# PS_mainPrint.net
KiCad netlist of a schematic drawn in Altium Designer
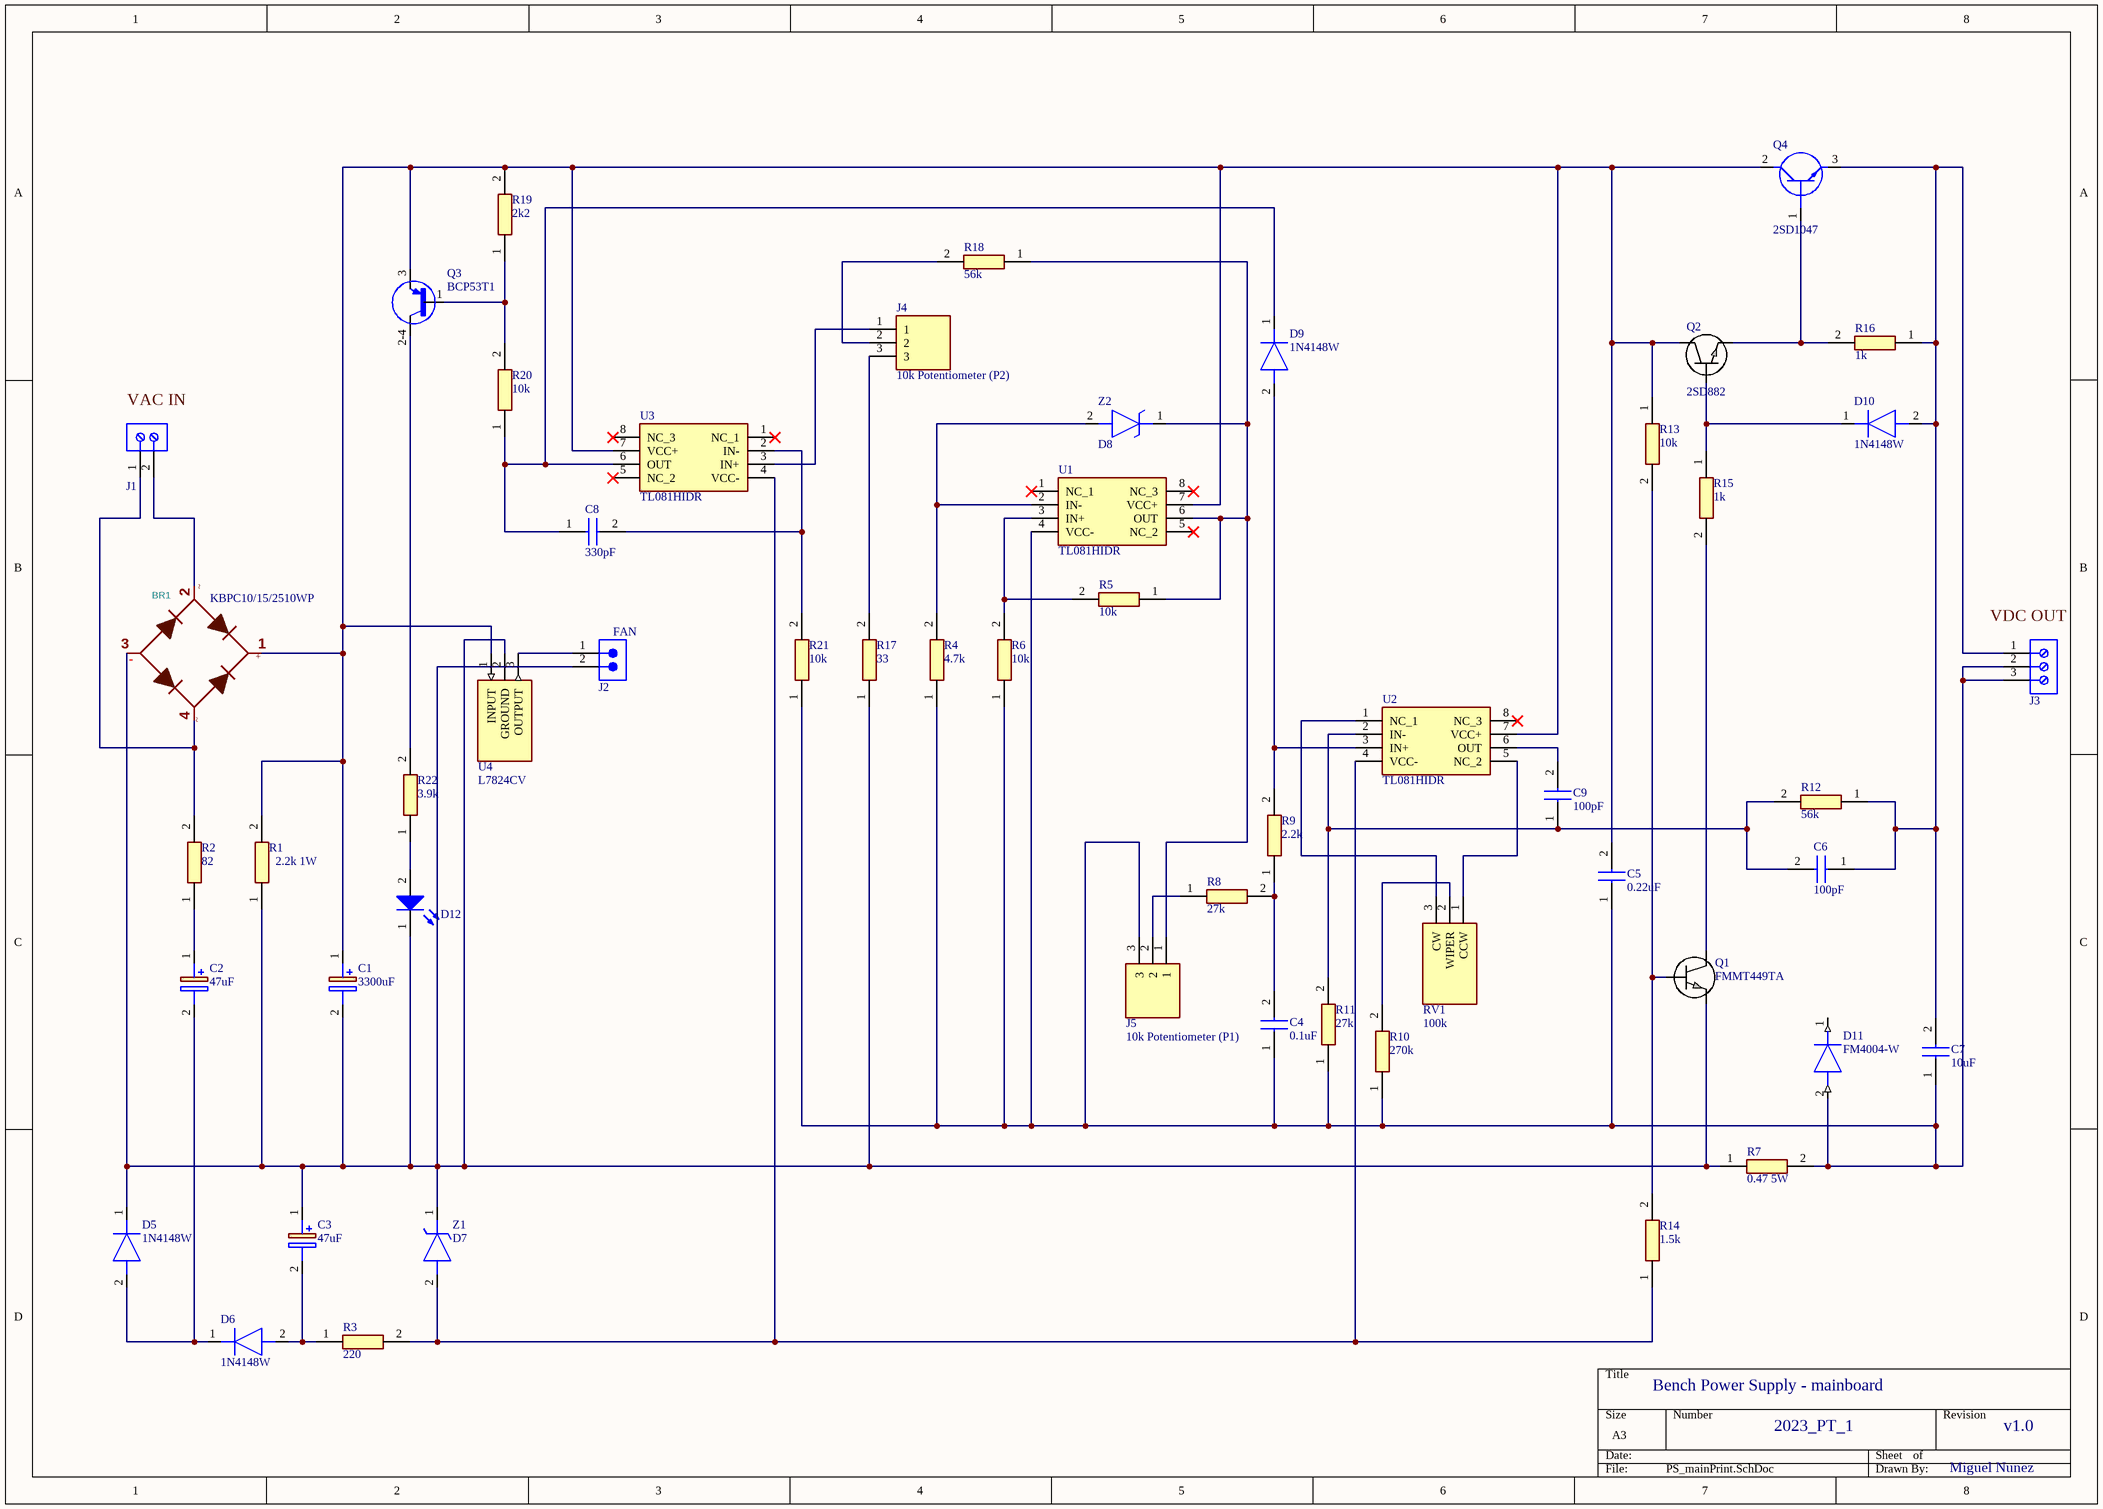
[diagram p0: PS_mainPrint.SchDoc]

(export (version "E")
  (design (tool "Eeschema 10.0.6"))
  (components
    (comp (ref "BR1")
      (value "KBPC10/15/2510WP")
      (footprint "PS_PcbLib:KBPCxxxxWP")
      (libsource (lib "PS_SchematicLib") (part "Bridge_1ph"))
    )
    (comp (ref "C1")
      (value "3300uF")
      (footprint "PS_PcbLib:CAPPRD500W60D1050H1350")
      (description "Capacitor Polarised MAL213668479E3")
      (fields
        (field (name "MANUFACTURER_PART_NUMBER") "MAL213668479E3")
        (field (name "MOUSER PART NUMBER") "594-2222-136-68479")
      )
      (libsource (lib "PS_SchematicLib") (part "MAL213668479E3"))
    )
    (comp (ref "C2")
      (value "47uF")
      (footprint "PS_PcbLib:CAPPRD750W80D1850H4250")
      (description "Capacitor Polarised MAL215051332E3")
      (fields
        (field (name "MANUFACTURER_PART_NUMBER") "MAL215051332E3")
        (field (name "MOUSER PART NUMBER") "594-MAL215051332E3")
      )
      (libsource (lib "PS_SchematicLib") (part "MAL215051332E3"))
    )
    (comp (ref "C3")
      (value "47uF")
      (footprint "PS_PcbLib:CAPPRD750W80D1850H4250")
      (description "Capacitor Polarised MAL215051332E3")
      (fields
        (field (name "MANUFACTURER_PART_NUMBER") "MAL215051332E3")
        (field (name "MOUSER PART NUMBER") "594-MAL215051332E3")
      )
      (libsource (lib "PS_SchematicLib") (part "MAL215051332E3"))
    )
    (comp (ref "C4")
      (value "0.1uF")
      (footprint "PS_PcbLib:CAPC2012X145N")
      (description "Capacitor C2012X7T2E104K125AE")
      (fields
        (field (name "MANUFACTURER_PART_NUMBER") "C2012X7T2E104K125AE")
        (field (name "MOUSER PART NUMBER") "810-C2012X7T2E104KST")
      )
      (libsource (lib "PS_SchematicLib") (part "Capacitor cer. 0805"))
    )
    (comp (ref "C5")
      (value "0.22uF")
      (footprint "PS_PcbLib:CAPC2012X145N")
      (description "Capacitor C2012X7T2E104K125AE")
      (fields
        (field (name "MANUFACTURER_PART_NUMBER") "C2012X7T2E104K125AE")
        (field (name "MOUSER PART NUMBER") "810-C2012X7T2E104KST")
      )
      (libsource (lib "PS_SchematicLib") (part "Capacitor cer. 0805"))
    )
    (comp (ref "C6")
      (value "100pF")
      (footprint "PS_PcbLib:CAPC2012X145N")
      (description "Capacitor C2012X7T2E104K125AE")
      (fields
        (field (name "MANUFACTURER_PART_NUMBER") "C2012X7T2E104K125AE")
        (field (name "MOUSER PART NUMBER") "810-C2012X7T2E104KST")
      )
      (libsource (lib "PS_SchematicLib") (part "Capacitor cer. 0805"))
    )
    (comp (ref "C7")
      (value "10uF")
      (footprint "PS_PcbLib:CAPC2012X145N")
      (description "Capacitor C2012X7T2E104K125AE")
      (fields
        (field (name "MANUFACTURER_PART_NUMBER") "C2012X7T2E104K125AE")
        (field (name "MOUSER PART NUMBER") "810-C2012X7T2E104KST")
      )
      (libsource (lib "PS_SchematicLib") (part "Capacitor cer. 0805"))
    )
    (comp (ref "C8")
      (value "330pF")
      (footprint "PS_PcbLib:CAPC2012X145N")
      (description "Capacitor C2012X7T2E104K125AE")
      (fields
        (field (name "MANUFACTURER_PART_NUMBER") "C2012X7T2E104K125AE")
        (field (name "MOUSER PART NUMBER") "810-C2012X7T2E104KST")
      )
      (libsource (lib "PS_SchematicLib") (part "Capacitor cer. 0805"))
    )
    (comp (ref "C9")
      (value "100pF")
      (footprint "PS_PcbLib:CAPC2012X145N")
      (description "Capacitor C2012X7T2E104K125AE")
      (fields
        (field (name "MANUFACTURER_PART_NUMBER") "C2012X7T2E104K125AE")
        (field (name "MOUSER PART NUMBER") "810-C2012X7T2E104KST")
      )
      (libsource (lib "PS_SchematicLib") (part "Capacitor cer. 0805"))
    )
    (comp (ref "D5")
      (value "1N4148W")
      (footprint "PS_PcbLib:SOD3816X135N")
      (description "Diode 1N4148W_R1_00001")
      (fields
        (field (name "MANUFACTURER_PART_NUMBER") "1N4148W_R1_00001")
        (field (name "MOUSER PART NUMBER") "241-1N4148W_R1_00001")
      )
      (libsource (lib "PS_SchematicLib") (part "1N4148W_R1_00001"))
    )
    (comp (ref "D6")
      (value "1N4148W")
      (footprint "PS_PcbLib:SOD3816X135N")
      (description "Diode 1N4148W_R1_00001")
      (fields
        (field (name "MANUFACTURER_PART_NUMBER") "1N4148W_R1_00001")
        (field (name "MOUSER PART NUMBER") "241-1N4148W_R1_00001")
      )
      (libsource (lib "PS_SchematicLib") (part "1N4148W_R1_00001"))
    )
    (comp (ref "D9")
      (value "1N4148W")
      (footprint "PS_PcbLib:SOD3816X135N")
      (description "Diode 1N4148W_R1_00001")
      (fields
        (field (name "MANUFACTURER_PART_NUMBER") "1N4148W_R1_00001")
        (field (name "MOUSER PART NUMBER") "241-1N4148W_R1_00001")
      )
      (libsource (lib "PS_SchematicLib") (part "1N4148W_R1_00001"))
    )
    (comp (ref "D10")
      (value "1N4148W")
      (footprint "PS_PcbLib:SOD3816X135N")
      (description "Diode 1N4148W_R1_00001")
      (fields
        (field (name "MANUFACTURER_PART_NUMBER") "1N4148W_R1_00001")
        (field (name "MOUSER PART NUMBER") "241-1N4148W_R1_00001")
      )
      (libsource (lib "PS_SchematicLib") (part "1N4148W_R1_00001"))
    )
    (comp (ref "D11")
      (value "FM4004-W")
      (footprint "PS_PcbLib:DIONM5025X231N")
      (description "Diode")
      (fields (field (name "MOUSER PART NUMBER") "583-FM4004"))
      (libsource (lib "PS_SchematicLib") (part "FM4004-W"))
    )
    (comp (ref "D12")
      (value "Blue, 3.2V, 140°")
      (footprint "PS_PcbLib:WL-SMCW_0805_150080xx75000")
      (description "WL-SMCW Mono-color Chip LED Waterclear, size 0805, Blue, 3.2V, 140°")
      (fields
        (field (name "MANUFACTURER PART NUMBER") "150080BS75000")
        (field (name "MANUFACTURER") "Wurth Elektronik")
      )
      (libsource (lib "PS_SchematicLib") (part "150080BS75000"))
    )
    (comp (ref "J1")
      (value "24VAC INPUT")
      (footprint "PS_PcbLib:691103110002")
      (description "WR-TBL Series 1031 Horizontal Entry Modular, THT, pitch 3.5mm, 2p 691103110002")
      (fields
        (field (name "MANUFACTURER PART NUMBER") "691103110002")
        (field (name "MANUFACTURER") "Wurth Elektronik")
      )
      (libsource (lib "PS_SchematicLib") (part "691103110002"))
    )
    (comp (ref "J2")
      (value "FAN")
      (footprint "PS_PcbLib:61900211121")
      (description "WR-WTB THT Male Vertical Locking Header, pitch 2.54mm, 2pins 61900211121")
      (fields
        (field (name "MANUFACTURER PART NUMBER") "61900211121")
        (field (name "MANUFACTURER") "Wurth Elektronik")
      )
      (libsource (lib "PS_SchematicLib") (part "61900211121"))
    )
    (comp (ref "J3")
      (value "TermBlock 3p")
      (footprint "PS_PcbLib:691103110003")
      (description "WR-TBL Series 1031 Horizontal Entry Modular, THT, pitch 3.5mm, 3p  691103110003")
      (fields
        (field (name "MANUFACTURER PART NUMBER") "691103110003")
        (field (name "MANUFACTURER") "Wurth Elektronik")
      )
      (libsource (lib "PS_SchematicLib") (part "691103110003"))
    )
    (comp (ref "J4")
      (value "10k Potentiometer (P2)")
      (footprint "PS_PcbLib:SHDR3W79P0X254_1X3_762X580X1175P")
      (description "Connector 3pin")
      (fields (field (name "MANUFACTURER_PART_NUMBER") "61900311121"))
      (libsource (lib "") (part "61900311121_1"))
    )
    (comp (ref "J5")
      (value "10k Potentiometer (P1)")
      (footprint "PS_PcbLib:SHDR3W79P0X254_1X3_762X580X1175P")
      (description "Connector 3pin")
      (fields (field (name "MANUFACTURER_PART_NUMBER") "61900311121"))
      (libsource (lib "PS_SchematicLib") (part "61900311121"))
    )
    (comp (ref "Q1")
      (value "FMMT449TA")
      (footprint "PS_PcbLib:SOT-23_2P9X1P3_DIO")
      (description "No Description Available")
      (fields (field (name "COPYRIGHT") "Copyright (C) 2023 Ultra Librarian. All rights reserved."))
      (libsource (lib "PS_SchematicLib") (part "FMMT449TA"))
    )
    (comp (ref "Q2")
      (value "2SD882")
      (footprint "PS_PcbLib:SOT-32_STM")
      (description "No Description Available")
      (fields (field (name "COPYRIGHT") "Copyright (C) 2023 Ultra Librarian. All rights reserved."))
      (libsource (lib "PS_SchematicLib") (part "2SD882"))
    )
    (comp (ref "Q3")
      (value "BCP53T1")
      (footprint "PS_PcbLib:TRANS_BCP53T1")
      (description "Bipolar (BJT) Transistor PNP 80 V 1.5 A 50MHz 1.5 W Surface Mount SOT-223 (TO-261)")
      (fields (field (name "MF") "ON Semiconductor"))
      (libsource (lib "PS_SchematicLib") (part "BCP53T1"))
    )
    (comp (ref "Q4")
      (value "2SD1047")
      (footprint "PS_PcbLib:TO545P500X1560X2360-3P")
      (description "Transistor BJT NPN")
      (fields (field (name "MOUSER PART NUMBER") "511-2SD1047"))
      (libsource (lib "PS_SchematicLib") (part "2SD1047"))
    )
    (comp (ref "R1")
      (value "2.2k 1W")
      (footprint "PS_PcbLib:RESC5025X70N")
      (description "Resistor 2.2k 1W CRCW20102K20JNEFHP")
      (fields (field (name "MANUFACTURER_PART_NUMBER") "ESR10EZPJ472"))
      (libsource (lib "") (part "CRCW2010_1"))
    )
    (comp (ref "R2")
      (value "82")
      (footprint "PS_PcbLib:RESC2012X60N")
      (description "Resistor CRCW0805")
      (fields
        (field (name "MANUFACTURER_PART_NUMBER") "CRCW080582R0FKEAHP")
        (field (name "MOUSER PART NUMBER") "71-CRCW080582R0FKEAH")
      )
      (libsource (lib "PS_SchematicLib") (part "CRCW0805"))
    )
    (comp (ref "R3")
      (value "220")
      (footprint "PS_PcbLib:RESC2012X60N")
      (description "Resistor CRCW0805")
      (fields
        (field (name "MANUFACTURER_PART_NUMBER") "CRCW080582R0FKEAHP")
        (field (name "MOUSER PART NUMBER") "71-CRCW080582R0FKEAH")
      )
      (libsource (lib "") (part "CRCW0805_1"))
    )
    (comp (ref "R4")
      (value "4.7k")
      (footprint "PS_PcbLib:RESC2012X60N")
      (description "Resistor CRCW0805")
      (fields
        (field (name "MANUFACTURER_PART_NUMBER") "CRCW080582R0FKEAHP")
        (field (name "MOUSER PART NUMBER") "71-CRCW080582R0FKEAH")
      )
      (libsource (lib "PS_SchematicLib") (part "CRCW0805"))
    )
    (comp (ref "R5")
      (value "10k")
      (footprint "PS_PcbLib:RESC2012X60N")
      (description "Resistor CRCW0805")
      (fields
        (field (name "MANUFACTURER_PART_NUMBER") "CRCW080582R0FKEAHP")
        (field (name "MOUSER PART NUMBER") "71-CRCW080582R0FKEAH")
      )
      (libsource (lib "") (part "CRCW0805_2"))
    )
    (comp (ref "R6")
      (value "10k")
      (footprint "PS_PcbLib:RESC2012X60N")
      (description "Resistor CRCW0805")
      (fields
        (field (name "MANUFACTURER_PART_NUMBER") "CRCW080582R0FKEAHP")
        (field (name "MOUSER PART NUMBER") "71-CRCW080582R0FKEAH")
      )
      (libsource (lib "PS_SchematicLib") (part "CRCW0805"))
    )
    (comp (ref "R7")
      (value "0.47 5W")
      (footprint "PS_PcbLib:RESAD4800W83L1800D750")
      (description "Resistor 0.47 5W AC05000004707JAC00")
      (fields
        (field (name "MANUFACTURER_PART_NUMBER") "AC05000004707JAC00")
        (field (name "MOUSER PART NUMBER") "594-AC05W0R470J")
      )
      (libsource (lib "PS_SchematicLib") (part "AC05000004707JAC00"))
    )
    (comp (ref "R8")
      (value "27k")
      (footprint "PS_PcbLib:RES_CRCW_1206_VIS-M")
      (description "Resistor CRCW1206")
      (fields
        (field (name "MANUFACTURER_PART_NUMBER") "CRCW080582R0FKEAHP")
        (field (name "MOUSER PART NUMBER") "71-CRCW080582R0FKEAH")
      )
      (libsource (lib "") (part "CRCW1206_1"))
    )
    (comp (ref "R9")
      (value "2.2k")
      (footprint "PS_PcbLib:RESC2012X60N")
      (description "Resistor CRCW0805")
      (fields
        (field (name "MANUFACTURER_PART_NUMBER") "CRCW080582R0FKEAHP")
        (field (name "MOUSER PART NUMBER") "71-CRCW080582R0FKEAH")
      )
      (libsource (lib "PS_SchematicLib") (part "CRCW0805"))
    )
    (comp (ref "R10")
      (value "270k")
      (footprint "PS_PcbLib:RESC5025X70N")
      (description "Resistor 270k CRCW20102K20JNEFHP")
      (fields (field (name "MANUFACTURER_PART_NUMBER") "ESR10EZPJ472"))
      (libsource (lib "") (part "CRCW2010_1"))
    )
    (comp (ref "R11")
      (value "27k")
      (footprint "PS_PcbLib:RES_CRCW_1206_VIS-M")
      (description "Resistor CRCW1206")
      (fields
        (field (name "MANUFACTURER_PART_NUMBER") "CRCW080582R0FKEAHP")
        (field (name "MOUSER PART NUMBER") "71-CRCW080582R0FKEAH")
      )
      (libsource (lib "PS_SchematicLib") (part "CRCW1206"))
    )
    (comp (ref "R12")
      (value "56k")
      (footprint "PS_PcbLib:RESC2012X60N")
      (description "Resistor CRCW0805")
      (fields
        (field (name "MANUFACTURER_PART_NUMBER") "CRCW080582R0FKEAHP")
        (field (name "MOUSER PART NUMBER") "71-CRCW080582R0FKEAH")
      )
      (libsource (lib "") (part "CRCW0805_2"))
    )
    (comp (ref "R13")
      (value "10k")
      (footprint "PS_PcbLib:RESC2012X60N")
      (description "Resistor CRCW0805")
      (fields
        (field (name "MANUFACTURER_PART_NUMBER") "CRCW080582R0FKEAHP")
        (field (name "MOUSER PART NUMBER") "71-CRCW080582R0FKEAH")
      )
      (libsource (lib "") (part "CRCW0805_3"))
    )
    (comp (ref "R14")
      (value "1.5k")
      (footprint "PS_PcbLib:RES_CRCW_1206_VIS-M")
      (description "Resistor 1.5k 1206")
      (fields
        (field (name "MANUFACTURER_PART_NUMBER") "CRCW080582R0FKEAHP")
        (field (name "MOUSER PART NUMBER") "71-CRCW080582R0FKEAH")
      )
      (libsource (lib "PS_SchematicLib") (part "CRCW1206"))
    )
    (comp (ref "R15")
      (value "1k")
      (footprint "PS_PcbLib:RESC5025X70N")
      (description "Resistor 270k CRCW20102K20JNEFHP")
      (fields (field (name "MANUFACTURER_PART_NUMBER") "ESR10EZPJ472"))
      (libsource (lib "") (part "CRCW2010_2"))
    )
    (comp (ref "R16")
      (value "1k")
      (footprint "PS_PcbLib:RESC5025X70N")
      (description "Resistor 270k CRCW20102K20JNEFHP")
      (fields (field (name "MANUFACTURER_PART_NUMBER") "ESR10EZPJ472"))
      (libsource (lib "PS_SchematicLib") (part "CRCW2010"))
    )
    (comp (ref "R17")
      (value "33")
      (footprint "PS_PcbLib:RESC2012X60N")
      (description "Resistor CRCW0805")
      (fields
        (field (name "MANUFACTURER_PART_NUMBER") "CRCW080582R0FKEAHP")
        (field (name "MOUSER PART NUMBER") "71-CRCW080582R0FKEAH")
      )
      (libsource (lib "PS_SchematicLib") (part "CRCW0805"))
    )
    (comp (ref "R18")
      (value "56k")
      (footprint "PS_PcbLib:RESC2012X60N")
      (description "Resistor CRCW0805")
      (fields
        (field (name "MANUFACTURER_PART_NUMBER") "CRCW080582R0FKEAHP")
        (field (name "MOUSER PART NUMBER") "71-CRCW080582R0FKEAH")
      )
      (libsource (lib "") (part "CRCW0805_2"))
    )
    (comp (ref "R19")
      (value "2k2")
      (footprint "PS_PcbLib:RESC2012X60N")
      (description "Resistor CRCW0805")
      (fields
        (field (name "MANUFACTURER_PART_NUMBER") "CRCW080582R0FKEAHP")
        (field (name "MOUSER PART NUMBER") "71-CRCW080582R0FKEAH")
      )
      (libsource (lib "PS_SchematicLib") (part "CRCW0805"))
    )
    (comp (ref "R20")
      (value "10k")
      (footprint "PS_PcbLib:RESC2012X60N")
      (description "Resistor CRCW0805")
      (fields
        (field (name "MANUFACTURER_PART_NUMBER") "CRCW080582R0FKEAHP")
        (field (name "MOUSER PART NUMBER") "71-CRCW080582R0FKEAH")
      )
      (libsource (lib "PS_SchematicLib") (part "CRCW0805"))
    )
    (comp (ref "R21")
      (value "10k")
      (footprint "PS_PcbLib:RESC2012X60N")
      (description "Resistor CRCW0805")
      (fields
        (field (name "MANUFACTURER_PART_NUMBER") "CRCW080582R0FKEAHP")
        (field (name "MOUSER PART NUMBER") "71-CRCW080582R0FKEAH")
      )
      (libsource (lib "PS_SchematicLib") (part "CRCW0805"))
    )
    (comp (ref "R22")
      (value "3.9k")
      (footprint "PS_PcbLib:RESC2012X60N")
      (description "Resistor CRCW0805")
      (fields
        (field (name "MANUFACTURER_PART_NUMBER") "CRCW080582R0FKEAHP")
        (field (name "MOUSER PART NUMBER") "71-CRCW080582R0FKEAH")
      )
      (libsource (lib "PS_SchematicLib") (part "CRCW0805"))
    )
    (comp (ref "RV1")
      (value "100k")
      (footprint "PS_PcbLib:3296W-1")
      (description "Variable Resistor 3296W-1-104LF")
      (fields
        (field (name "MANUFACTURER_PART_NUMBER") "3296W-1-104LF")
        (field (name "MOUSER PART NUMBER") "652-3296W-1-104LF")
      )
      (libsource (lib "PS_SchematicLib") (part "3296W-1-104LF"))
    )
    (comp (ref "U1")
      (value "TL081HIDR")
      (footprint "PS_PcbLib:SOIC127P600X175-8N")
      (description "Integrated Circuit")
      (fields (field (name "MOUSER PART NUMBER") "595-TL081HIDR"))
      (libsource (lib "PS_SchematicLib") (part "TL081HIDR"))
    )
    (comp (ref "U2")
      (value "TL081HIDR")
      (footprint "PS_PcbLib:SOIC127P600X175-8N")
      (description "Integrated Circuit")
      (fields (field (name "MOUSER PART NUMBER") "595-TL081HIDR"))
      (libsource (lib "PS_SchematicLib") (part "TL081HIDR"))
    )
    (comp (ref "U3")
      (value "TL081HIDR")
      (footprint "PS_PcbLib:SOIC127P600X175-8N")
      (description "Integrated Circuit")
      (fields (field (name "MOUSER PART NUMBER") "595-TL081HIDR"))
      (libsource (lib "") (part "TL081HIDR_1"))
    )
    (comp (ref "U4")
      (value "L7824CV")
      (footprint "PS_PcbLib:TO270P460X1020X2008-3P")
      (description "Integrated Circuit LDO 24V")
      (fields (field (name "MOUSER PART NUMBER") "511-L7824CV"))
      (libsource (lib "PS_SchematicLib") (part "L7824CV"))
    )
    (comp (ref "Z1")
      (value "D7")
      (footprint "PS_PcbLib:SOD3716X135N")
      (description "Zener Diode BZT52C5V1-E3-08")
      (fields
        (field (name "MANUFACTURER_PART_NUMBER") "BZT52C5V1-E3-08")
        (field (name "MOUSER PART NUMBER") "78-BZT52C5V1-E3-08")
      )
      (libsource (lib "PS_SchematicLib") (part "BZT52C5V1-E3-08"))
    )
    (comp (ref "Z2")
      (value "D8")
      (footprint "PS_PcbLib:SOD3716X135N")
      (description "Zener Diode BZT52C5V1-E3-08")
      (fields
        (field (name "MANUFACTURER_PART_NUMBER") "BZT52C5V1-E3-08")
        (field (name "MOUSER PART NUMBER") "78-BZT52C5V1-E3-08")
      )
      (libsource (lib "PS_SchematicLib") (part "BZT52C5V1-E3-08"))
    )
  )
  (nets
    (net (code "1") (name "Net-(BR1-+)") (class "Default")
      (node (ref "BR1") (pin "1") (pinfunction "+_1") (pintype "passive"))
      (node (ref "C1") (pin "1") (pinfunction "+_1") (pintype "passive"))
      (node (ref "C5") (pin "2") (pinfunction "2_2") (pintype "passive"))
      (node (ref "Q2") (pin "2") (pinfunction "C_2") (pintype "passive"))
      (node (ref "Q3") (pin "3") (pinfunction "E_3") (pintype "passive"))
      (node (ref "Q4") (pin "2") (pinfunction "C_2") (pintype "passive"))
      (node (ref "R1") (pin "2") (pinfunction "2_2") (pintype "passive"))
      (node (ref "R13") (pin "1") (pinfunction "1_1") (pintype "passive"))
      (node (ref "R19") (pin "2") (pinfunction "2_2") (pintype "passive"))
      (node (ref "U1") (pin "7") (pinfunction "VCC+_7") (pintype "passive"))
      (node (ref "U2") (pin "7") (pinfunction "VCC+_7") (pintype "passive"))
      (node (ref "U3") (pin "7") (pinfunction "VCC+_7") (pintype "passive"))
      (node (ref "U4") (pin "1") (pinfunction "INPUT_1") (pintype "input"))
    )
    (net (code "2") (name "Net-(BR1--)") (class "Default")
      (node (ref "BR1") (pin "3") (pinfunction "-_3") (pintype "passive"))
      (node (ref "C1") (pin "2") (pinfunction "-_2") (pintype "passive"))
      (node (ref "C3") (pin "1") (pinfunction "+_1") (pintype "passive"))
      (node (ref "D12") (pin "1") (pinfunction "K_1") (pintype "passive"))
      (node (ref "D5") (pin "1") (pinfunction "K_1") (pintype "passive"))
      (node (ref "J2") (pin "2") (pinfunction "2_2") (pintype "passive"))
      (node (ref "Q1") (pin "3") (pinfunction "VCC_3") (pintype "power_in"))
      (node (ref "R1") (pin "1") (pinfunction "1_1") (pintype "passive"))
      (node (ref "R17") (pin "1") (pinfunction "1_1") (pintype "passive"))
      (node (ref "R7") (pin "1") (pinfunction "1_1") (pintype "passive"))
      (node (ref "U4") (pin "2") (pinfunction "GROUND_2") (pintype "power_in"))
      (node (ref "Z1") (pin "1") (pinfunction "K_1") (pintype "passive"))
    )
    (net (code "3") (name "Net-(BR1-Input_~-Pad2)") (class "Default")
      (node (ref "BR1") (pin "2") (pinfunction "Input_~_2") (pintype "passive"))
      (node (ref "J1") (pin "2") (pinfunction "2_2") (pintype "passive"))
    )
    (net (code "4") (name "Net-(BR1-Input_~-Pad4)") (class "Default")
      (node (ref "BR1") (pin "4") (pinfunction "Input_~_4") (pintype "passive"))
      (node (ref "J1") (pin "1") (pinfunction "1_1") (pintype "passive"))
      (node (ref "R2") (pin "2") (pinfunction "2_2") (pintype "passive"))
    )
    (net (code "5") (name "Net-(C2-+)") (class "Default")
      (node (ref "C2") (pin "1") (pinfunction "+_1") (pintype "passive"))
      (node (ref "R2") (pin "1") (pinfunction "1_1") (pintype "passive"))
    )
    (net (code "6") (name "Net-(C2--)") (class "Default")
      (node (ref "C2") (pin "2") (pinfunction "-_2") (pintype "passive"))
      (node (ref "D5") (pin "2") (pinfunction "A_2") (pintype "passive"))
      (node (ref "D6") (pin "1") (pinfunction "K_1") (pintype "passive"))
    )
    (net (code "7") (name "Net-(C3--)") (class "Default")
      (node (ref "C3") (pin "2") (pinfunction "-_2") (pintype "passive"))
      (node (ref "D6") (pin "2") (pinfunction "A_2") (pintype "passive"))
      (node (ref "R3") (pin "1") (pinfunction "1_1") (pintype "passive"))
    )
    (net (code "8") (name "Net-(C4-Pad2)") (class "Default")
      (node (ref "C4") (pin "2") (pinfunction "2_2") (pintype "passive"))
      (node (ref "R8") (pin "2") (pinfunction "2_2") (pintype "passive"))
      (node (ref "R9") (pin "1") (pinfunction "1_1") (pintype "passive"))
    )
    (net (code "9") (name "Net-(D9-A)") (class "Default")
      (node (ref "D9") (pin "2") (pinfunction "A_2") (pintype "passive"))
      (node (ref "R9") (pin "2") (pinfunction "2_2") (pintype "passive"))
      (node (ref "U2") (pin "3") (pinfunction "IN+_3") (pintype "passive"))
    )
    (net (code "10") (name "Net-(D9-K)") (class "Default")
      (node (ref "C8") (pin "1") (pinfunction "1_1") (pintype "passive"))
      (node (ref "D9") (pin "1") (pinfunction "K_1") (pintype "passive"))
      (node (ref "R20") (pin "1") (pinfunction "1_1") (pintype "passive"))
      (node (ref "U3") (pin "6") (pinfunction "OUT_6") (pintype "passive"))
    )
    (net (code "11") (name "Net-(D10-A)") (class "Default")
      (node (ref "C6") (pin "1") (pinfunction "1_1") (pintype "passive"))
      (node (ref "C7") (pin "2") (pinfunction "2_2") (pintype "passive"))
      (node (ref "D10") (pin "2") (pinfunction "A_2") (pintype "passive"))
      (node (ref "J3") (pin "1") (pinfunction "1_1") (pintype "passive"))
      (node (ref "Q4") (pin "3") (pinfunction "E_3") (pintype "passive"))
      (node (ref "R12") (pin "1") (pinfunction "1_1") (pintype "passive"))
      (node (ref "R16") (pin "1") (pinfunction "1_1") (pintype "passive"))
    )
    (net (code "12") (name "Net-(D10-K)") (class "Default")
      (node (ref "D10") (pin "1") (pinfunction "K_1") (pintype "passive"))
      (node (ref "Q2") (pin "1") (pinfunction "B_1") (pintype "passive"))
      (node (ref "R15") (pin "1") (pinfunction "1_1") (pintype "passive"))
    )
    (net (code "13") (name "Net-(D11-A)") (class "Default")
      (node (ref "C4") (pin "1") (pinfunction "1_1") (pintype "passive"))
      (node (ref "C5") (pin "1") (pinfunction "1_1") (pintype "passive"))
      (node (ref "C7") (pin "1") (pinfunction "1_1") (pintype "passive"))
      (node (ref "D11") (pin "2") (pinfunction "A_2") (pintype "input"))
      (node (ref "J3") (pin "2") (pinfunction "2_2") (pintype "passive"))
      (node (ref "J3") (pin "3") (pinfunction "3_3") (pintype "passive"))
      (node (ref "J5") (pin "3") (pinfunction "3_3") (pintype "passive"))
      (node (ref "R10") (pin "1") (pinfunction "1_1") (pintype "passive"))
      (node (ref "R11") (pin "1") (pinfunction "1_1") (pintype "passive"))
      (node (ref "R21") (pin "1") (pinfunction "1_1") (pintype "passive"))
      (node (ref "R4") (pin "1") (pinfunction "1_1") (pintype "passive"))
      (node (ref "R6") (pin "1") (pinfunction "1_1") (pintype "passive"))
      (node (ref "R7") (pin "2") (pinfunction "2_2") (pintype "passive"))
      (node (ref "U1") (pin "4") (pinfunction "VCC-_4") (pintype "passive"))
    )
    (net (code "14") (name "Net-(D12-A)") (class "Default")
      (node (ref "D12") (pin "2") (pinfunction "A_2") (pintype "passive"))
      (node (ref "R22") (pin "1") (pinfunction "1_1") (pintype "passive"))
    )
    (net (code "15") (name "Net-(J4-Pad2)") (class "Default")
      (node (ref "J4") (pin "2") (pinfunction "2_2") (pintype "passive"))
      (node (ref "R18") (pin "2") (pinfunction "2_2") (pintype "passive"))
    )
    (net (code "16") (name "Net-(J4-Pad3)") (class "Default")
      (node (ref "J4") (pin "3") (pinfunction "3_3") (pintype "passive"))
      (node (ref "R17") (pin "2") (pinfunction "2_2") (pintype "passive"))
    )
    (net (code "17") (name "Net-(J5-Pad2)") (class "Default")
      (node (ref "J5") (pin "2") (pinfunction "2_2") (pintype "passive"))
      (node (ref "R8") (pin "1") (pinfunction "1_1") (pintype "passive"))
    )
    (net (code "18") (name "Net-(Q1-GND)") (class "Default")
      (node (ref "Q1") (pin "1") (pinfunction "GND_1") (pintype "power_in"))
      (node (ref "R13") (pin "2") (pinfunction "2_2") (pintype "passive"))
      (node (ref "R14") (pin "2") (pinfunction "2_2") (pintype "passive"))
    )
    (net (code "19") (name "Net-(Q1-RESET)") (class "Default")
      (node (ref "Q1") (pin "2") (pinfunction "RESET_2") (pintype "passive"))
      (node (ref "R15") (pin "2") (pinfunction "2_2") (pintype "passive"))
    )
    (net (code "20") (name "Net-(Q2-E)") (class "Default")
      (node (ref "Q2") (pin "3") (pinfunction "E_3") (pintype "passive"))
      (node (ref "Q4") (pin "1") (pinfunction "B_1") (pintype "passive"))
      (node (ref "R16") (pin "2") (pinfunction "2_2") (pintype "passive"))
    )
    (net (code "21") (name "Net-(Q3-B)") (class "Default")
      (node (ref "Q3") (pin "1") (pinfunction "B_1") (pintype "passive"))
      (node (ref "R19") (pin "1") (pinfunction "1_1") (pintype "passive"))
      (node (ref "R20") (pin "2") (pinfunction "2_2") (pintype "passive"))
    )
    (net (code "22") (name "Net-(Q3-C-Pad2-4)") (class "Default")
      (node (ref "Q3") (pin "2-4") (pinfunction "C_2-4") (pintype "passive"))
      (node (ref "R22") (pin "2") (pinfunction "2_2") (pintype "passive"))
    )
    (net (code "23") (name "Net-(RV1-CCW)") (class "Default")
      (node (ref "RV1") (pin "1") (pinfunction "CCW_1") (pintype "passive"))
      (node (ref "U2") (pin "5") (pinfunction "NC_2_5") (pintype "passive"))
    )
    (net (code "24") (name "Net-(RV1-CW)") (class "Default")
      (node (ref "RV1") (pin "3") (pinfunction "CW_3") (pintype "passive"))
      (node (ref "U2") (pin "1") (pinfunction "NC_1_1") (pintype "passive"))
    )
    (net (code "25") (name "Net-(RV1-WIPER)") (class "Default")
      (node (ref "R10") (pin "2") (pinfunction "2_2") (pintype "passive"))
      (node (ref "RV1") (pin "2") (pinfunction "WIPER_2") (pintype "passive"))
    )
    (net (code "26") (name "Net-(U1-IN+)") (class "Default")
      (node (ref "R5") (pin "2") (pinfunction "2_2") (pintype "passive"))
      (node (ref "R6") (pin "2") (pinfunction "2_2") (pintype "passive"))
      (node (ref "U1") (pin "3") (pinfunction "IN+_3") (pintype "passive"))
    )
    (net (code "27") (name "Net-(U1-IN-)") (class "Default")
      (node (ref "R4") (pin "2") (pinfunction "2_2") (pintype "passive"))
      (node (ref "U1") (pin "2") (pinfunction "IN-_2") (pintype "passive"))
      (node (ref "Z2") (pin "2") (pinfunction "A_2") (pintype "passive"))
    )
    (net (code "28") (name "Net-(U1-OUT)") (class "Default")
      (node (ref "J5") (pin "1") (pinfunction "1_1") (pintype "passive"))
      (node (ref "R18") (pin "1") (pinfunction "1_1") (pintype "passive"))
      (node (ref "R5") (pin "1") (pinfunction "1_1") (pintype "passive"))
      (node (ref "U1") (pin "6") (pinfunction "OUT_6") (pintype "passive"))
      (node (ref "Z2") (pin "1") (pinfunction "K_1") (pintype "passive"))
    )
    (net (code "29") (name "Net-(U2-IN-)") (class "Default")
      (node (ref "C6") (pin "2") (pinfunction "2_2") (pintype "passive"))
      (node (ref "C9") (pin "1") (pinfunction "1_1") (pintype "passive"))
      (node (ref "R11") (pin "2") (pinfunction "2_2") (pintype "passive"))
      (node (ref "R12") (pin "2") (pinfunction "2_2") (pintype "passive"))
      (node (ref "U2") (pin "2") (pinfunction "IN-_2") (pintype "passive"))
    )
    (net (code "30") (name "Net-(U2-OUT)") (class "Default")
      (node (ref "C9") (pin "2") (pinfunction "2_2") (pintype "passive"))
      (node (ref "U2") (pin "6") (pinfunction "OUT_6") (pintype "passive"))
    )
    (net (code "31") (name "Net-(U2-VCC-)") (class "Default")
      (node (ref "R14") (pin "1") (pinfunction "1_1") (pintype "passive"))
      (node (ref "R3") (pin "2") (pinfunction "2_2") (pintype "passive"))
      (node (ref "U2") (pin "4") (pinfunction "VCC-_4") (pintype "passive"))
      (node (ref "U3") (pin "4") (pinfunction "VCC-_4") (pintype "passive"))
      (node (ref "Z1") (pin "2") (pinfunction "A_2") (pintype "passive"))
    )
    (net (code "32") (name "Net-(U3-IN+)") (class "Default")
      (node (ref "J4") (pin "1") (pinfunction "1_1") (pintype "passive"))
      (node (ref "U3") (pin "3") (pinfunction "IN+_3") (pintype "passive"))
    )
    (net (code "33") (name "Net-(U3-IN-)") (class "Default")
      (node (ref "C8") (pin "2") (pinfunction "2_2") (pintype "passive"))
      (node (ref "R21") (pin "2") (pinfunction "2_2") (pintype "passive"))
      (node (ref "U3") (pin "2") (pinfunction "IN-_2") (pintype "passive"))
    )
    (net (code "34") (name "Net-(U4-OUTPUT)") (class "Default")
      (node (ref "J2") (pin "1") (pinfunction "1_1") (pintype "passive"))
      (node (ref "U4") (pin "3") (pinfunction "OUTPUT_3") (pintype "output"))
    )
    (net (code "35") (name "unconnected-(D11-K-Pad1)") (class "Default")
      (node (ref "D11") (pin "1") (pinfunction "K_1") (pintype "output"))
    )
    (net (code "36") (name "unconnected-(Q3-C-Pad2)") (class "Default")
      (node (ref "Q3") (pin "2") (pinfunction "C_2") (pintype "passive"))
    )
    (net (code "37") (name "unconnected-(U1-NC_1-Pad1)") (class "Default")
      (node (ref "U1") (pin "1") (pinfunction "NC_1_1") (pintype "passive+no_connect"))
    )
    (net (code "38") (name "unconnected-(U1-NC_2-Pad5)") (class "Default")
      (node (ref "U1") (pin "5") (pinfunction "NC_2_5") (pintype "passive+no_connect"))
    )
    (net (code "39") (name "unconnected-(U1-NC_3-Pad8)") (class "Default")
      (node (ref "U1") (pin "8") (pinfunction "NC_3_8") (pintype "passive+no_connect"))
    )
    (net (code "40") (name "unconnected-(U2-NC_3-Pad8)") (class "Default")
      (node (ref "U2") (pin "8") (pinfunction "NC_3_8") (pintype "passive+no_connect"))
    )
    (net (code "41") (name "unconnected-(U3-NC_1-Pad1)") (class "Default")
      (node (ref "U3") (pin "1") (pinfunction "NC_1_1") (pintype "passive+no_connect"))
    )
    (net (code "42") (name "unconnected-(U3-NC_2-Pad5)") (class "Default")
      (node (ref "U3") (pin "5") (pinfunction "NC_2_5") (pintype "passive+no_connect"))
    )
    (net (code "43") (name "unconnected-(U3-NC_3-Pad8)") (class "Default")
      (node (ref "U3") (pin "8") (pinfunction "NC_3_8") (pintype "passive+no_connect"))
    )
  )
)
